# pov.net
KiCad netlist of a schematic drawn in EAGLE
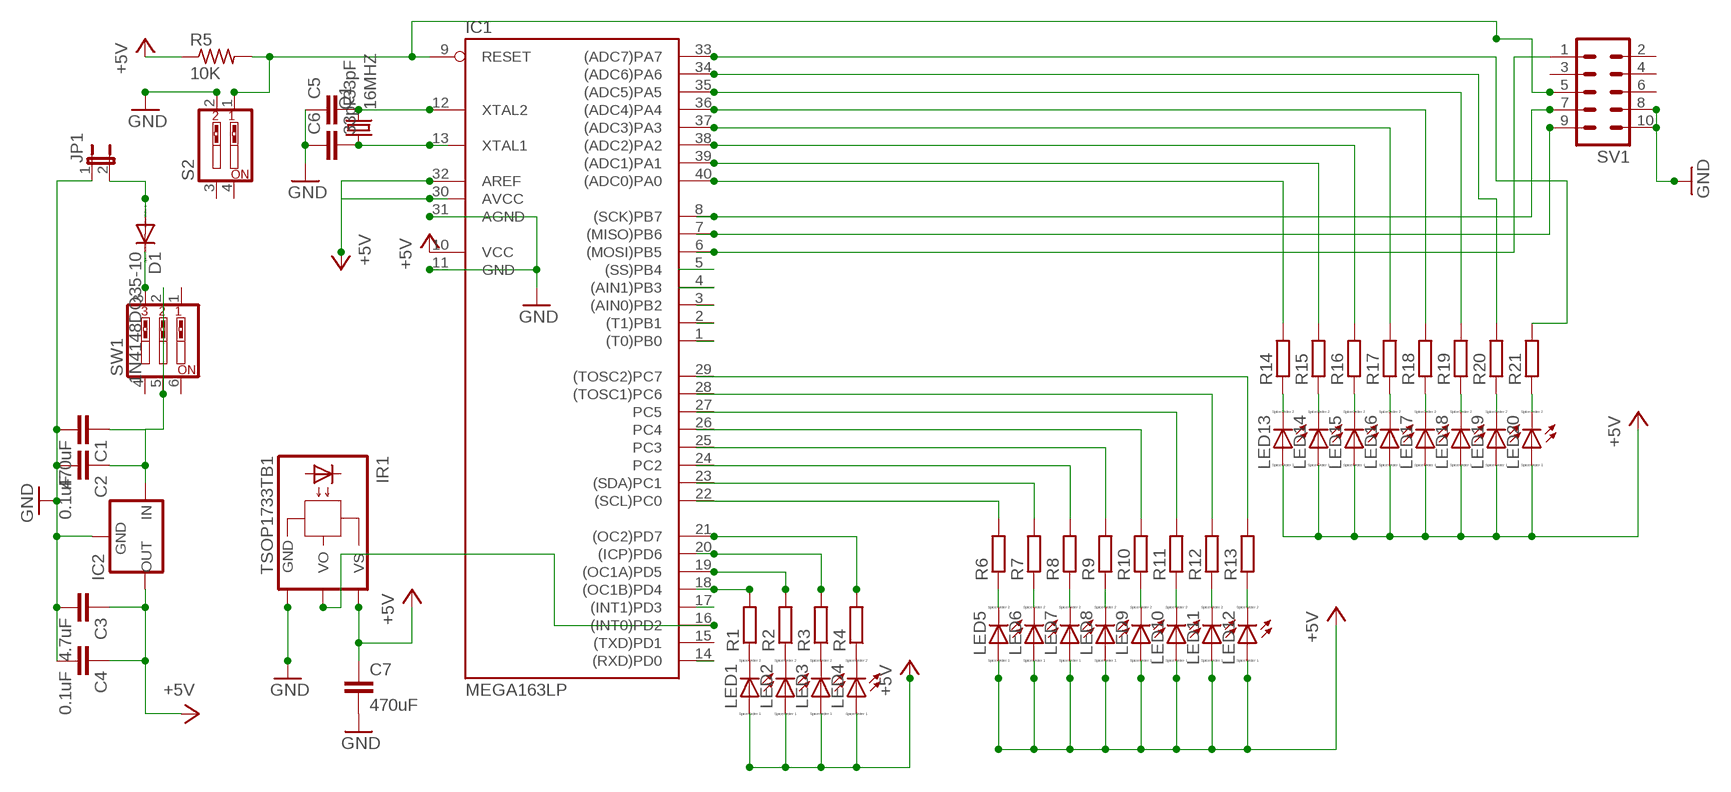
[diagram p0: schematic, sheet 1]

(export (version "E")
  (design (tool "Eeschema 10.0.6"))
  (components
    (comp (ref "C1")
      (value "470uF")
      (footprint "eagle-import:C2.5-4")
      (libsource (lib "eagle-import") (part "C2.5/4"))
    )
    (comp (ref "C2")
      (value "0.1uF")
      (footprint "eagle-import:C2.5-4")
      (libsource (lib "eagle-import") (part "C2.5/4"))
    )
    (comp (ref "C3")
      (value "4.7uF")
      (footprint "eagle-import:C2.5-4")
      (libsource (lib "eagle-import") (part "C2.5/4"))
    )
    (comp (ref "C4")
      (value "0.1uF")
      (footprint "eagle-import:C2.5-4")
      (libsource (lib "eagle-import") (part "C2.5/4"))
    )
    (comp (ref "C5")
      (value "33pF")
      (footprint "eagle-import:C2.5-4")
      (libsource (lib "eagle-import") (part "C2.5/4"))
    )
    (comp (ref "C6")
      (value "33pF")
      (footprint "eagle-import:C2.5-4")
      (libsource (lib "eagle-import") (part "C2.5/4"))
    )
    (comp (ref "C7")
      (value "470uF")
      (footprint "eagle-import:C2.5-4")
      (libsource (lib "eagle-import") (part "C2.5/4"))
    )
    (comp (ref "D1")
      (value "1N4148DO35-10")
      (footprint "eagle-import:DO35-10")
      (libsource (lib "eagle-import") (part "1N4148DO35-10"))
    )
    (comp (ref "IC1")
      (value "MEGA163LP")
      (footprint "eagle-import:DIL40")
      (libsource (lib "eagle-import") (part "MEGA163PL"))
    )
    (comp (ref "IC2")
      (value "78XXS")
      (footprint "eagle-import:78XXS")
      (libsource (lib "eagle-import") (part "78XXS"))
    )
    (comp (ref "IR1")
      (value "TSOP1733TB1")
      (footprint "eagle-import:TSOP17_TB1")
      (libsource (lib "eagle-import") (part "TSOP17TB133"))
    )
    (comp (ref "JP1")
      (value "JP1E")
      (footprint "eagle-import:JP1")
      (libsource (lib "eagle-import") (part "JP1E"))
    )
    (comp (ref "LED1")
      (value "LED_ELD260")
      (footprint "eagle-import:LED_LD260")
      (libsource (lib "eagle-import") (part "LED_ELD260"))
    )
    (comp (ref "LED2")
      (value "LED_ELD260")
      (footprint "eagle-import:LED_LD260")
      (libsource (lib "eagle-import") (part "LED_ELD260"))
    )
    (comp (ref "LED3")
      (value "LED_ELD260")
      (footprint "eagle-import:LED_LD260")
      (libsource (lib "eagle-import") (part "LED_ELD260"))
    )
    (comp (ref "LED4")
      (value "LED_ELD260")
      (footprint "eagle-import:LED_LD260")
      (libsource (lib "eagle-import") (part "LED_ELD260"))
    )
    (comp (ref "LED5")
      (value "LED_ELD260")
      (footprint "eagle-import:LED_LD260")
      (libsource (lib "eagle-import") (part "LED_ELD260"))
    )
    (comp (ref "LED6")
      (value "LED_ELD260")
      (footprint "eagle-import:LED_LD260")
      (libsource (lib "eagle-import") (part "LED_ELD260"))
    )
    (comp (ref "LED7")
      (value "LED_ELD260")
      (footprint "eagle-import:LED_LD260")
      (libsource (lib "eagle-import") (part "LED_ELD260"))
    )
    (comp (ref "LED8")
      (value "LED_ELD260")
      (footprint "eagle-import:LED_LD260")
      (libsource (lib "eagle-import") (part "LED_ELD260"))
    )
    (comp (ref "LED9")
      (value "LED_ELD260")
      (footprint "eagle-import:LED_LD260")
      (libsource (lib "eagle-import") (part "LED_ELD260"))
    )
    (comp (ref "LED10")
      (value "LED_ELD260")
      (footprint "eagle-import:LED_LD260")
      (libsource (lib "eagle-import") (part "LED_ELD260"))
    )
    (comp (ref "LED11")
      (value "LED_ELD260")
      (footprint "eagle-import:LED_LD260")
      (libsource (lib "eagle-import") (part "LED_ELD260"))
    )
    (comp (ref "LED12")
      (value "LED_ELD260")
      (footprint "eagle-import:LED_LD260")
      (libsource (lib "eagle-import") (part "LED_ELD260"))
    )
    (comp (ref "LED13")
      (value "LED_ELD260")
      (footprint "eagle-import:LED_LD260")
      (libsource (lib "eagle-import") (part "LED_ELD260"))
    )
    (comp (ref "LED14")
      (value "LED_ELD260")
      (footprint "eagle-import:LED_LD260")
      (libsource (lib "eagle-import") (part "LED_ELD260"))
    )
    (comp (ref "LED15")
      (value "LED_ELD260")
      (footprint "eagle-import:LED_LD260")
      (libsource (lib "eagle-import") (part "LED_ELD260"))
    )
    (comp (ref "LED16")
      (value "LED_ELD260")
      (footprint "eagle-import:LED_LD260")
      (libsource (lib "eagle-import") (part "LED_ELD260"))
    )
    (comp (ref "LED17")
      (value "LED_ELD260")
      (footprint "eagle-import:LED_LD260")
      (libsource (lib "eagle-import") (part "LED_ELD260"))
    )
    (comp (ref "LED18")
      (value "LED_ELD260")
      (footprint "eagle-import:LED_LD260")
      (libsource (lib "eagle-import") (part "LED_ELD260"))
    )
    (comp (ref "LED19")
      (value "LED_ELD260")
      (footprint "eagle-import:LED_LD260")
      (libsource (lib "eagle-import") (part "LED_ELD260"))
    )
    (comp (ref "LED20")
      (value "LED_ELD260")
      (footprint "eagle-import:LED_LD260")
      (libsource (lib "eagle-import") (part "LED_ELD260"))
    )
    (comp (ref "Q1")
      (value "16MHZ")
      (footprint "eagle-import:HC49U-V")
      (libsource (lib "eagle-import") (part "CRYSTALHC49U-V"))
    )
    (comp (ref "R1")
      (value "R-EU_0207/7")
      (footprint "eagle-import:0207_7")
      (libsource (lib "eagle-import") (part "R-EU_0207/7"))
    )
    (comp (ref "R2")
      (value "R-EU_0207/7")
      (footprint "eagle-import:0207_7")
      (libsource (lib "eagle-import") (part "R-EU_0207/7"))
    )
    (comp (ref "R3")
      (value "R-EU_0207/7")
      (footprint "eagle-import:0207_7")
      (libsource (lib "eagle-import") (part "R-EU_0207/7"))
    )
    (comp (ref "R4")
      (value "R-EU_0207/7")
      (footprint "eagle-import:0207_7")
      (libsource (lib "eagle-import") (part "R-EU_0207/7"))
    )
    (comp (ref "R5")
      (value "10K")
      (footprint "eagle-import:0204_7")
      (libsource (lib "eagle-import") (part "R-US_0204/7"))
    )
    (comp (ref "R6")
      (value "R-EU_0207/7")
      (footprint "eagle-import:0207_7")
      (libsource (lib "eagle-import") (part "R-EU_0207/7"))
    )
    (comp (ref "R7")
      (value "R-EU_0207/7")
      (footprint "eagle-import:0207_7")
      (libsource (lib "eagle-import") (part "R-EU_0207/7"))
    )
    (comp (ref "R8")
      (value "R-EU_0207/7")
      (footprint "eagle-import:0207_7")
      (libsource (lib "eagle-import") (part "R-EU_0207/7"))
    )
    (comp (ref "R9")
      (value "R-EU_0207/7")
      (footprint "eagle-import:0207_7")
      (libsource (lib "eagle-import") (part "R-EU_0207/7"))
    )
    (comp (ref "R10")
      (value "R-EU_0207/7")
      (footprint "eagle-import:0207_7")
      (libsource (lib "eagle-import") (part "R-EU_0207/7"))
    )
    (comp (ref "R11")
      (value "R-EU_0207/7")
      (footprint "eagle-import:0207_7")
      (libsource (lib "eagle-import") (part "R-EU_0207/7"))
    )
    (comp (ref "R12")
      (value "R-EU_0207/7")
      (footprint "eagle-import:0207_7")
      (libsource (lib "eagle-import") (part "R-EU_0207/7"))
    )
    (comp (ref "R13")
      (value "R-EU_0207/7")
      (footprint "eagle-import:0207_7")
      (libsource (lib "eagle-import") (part "R-EU_0207/7"))
    )
    (comp (ref "R14")
      (value "R-EU_0207/7")
      (footprint "eagle-import:0207_7")
      (libsource (lib "eagle-import") (part "R-EU_0207/7"))
    )
    (comp (ref "R15")
      (value "R-EU_0207/7")
      (footprint "eagle-import:0207_7")
      (libsource (lib "eagle-import") (part "R-EU_0207/7"))
    )
    (comp (ref "R16")
      (value "R-EU_0207/7")
      (footprint "eagle-import:0207_7")
      (libsource (lib "eagle-import") (part "R-EU_0207/7"))
    )
    (comp (ref "R17")
      (value "R-EU_0207/7")
      (footprint "eagle-import:0207_7")
      (libsource (lib "eagle-import") (part "R-EU_0207/7"))
    )
    (comp (ref "R18")
      (value "R-EU_0207/7")
      (footprint "eagle-import:0207_7")
      (libsource (lib "eagle-import") (part "R-EU_0207/7"))
    )
    (comp (ref "R19")
      (value "R-EU_0207/7")
      (footprint "eagle-import:0207_7")
      (libsource (lib "eagle-import") (part "R-EU_0207/7"))
    )
    (comp (ref "R20")
      (value "R-EU_0207/7")
      (footprint "eagle-import:0207_7")
      (libsource (lib "eagle-import") (part "R-EU_0207/7"))
    )
    (comp (ref "R21")
      (value "R-EU_0207/7")
      (footprint "eagle-import:0207_7")
      (libsource (lib "eagle-import") (part "R-EU_0207/7"))
    )
    (comp (ref "S2")
      (value "SW_DIP-2")
      (footprint "eagle-import:EDG-02")
      (libsource (lib "eagle-import") (part "SW_DIP-2"))
    )
    (comp (ref "SV1")
      (value "MA05-2")
      (footprint "eagle-import:MA05-2")
      (libsource (lib "eagle-import") (part "MA05-2"))
    )
    (comp (ref "SW1")
      (value "SW_DIP-3")
      (footprint "eagle-import:EDG-03")
      (libsource (lib "eagle-import") (part "SW_DIP-3"))
    )
  )
  (nets
    (net (code "1") (name "+5V") (class "Default")
      (node (ref "C3") (pin "1") (pinfunction "1_1") (pintype "passive"))
      (node (ref "C4") (pin "1") (pinfunction "1_1") (pintype "passive"))
      (node (ref "C7") (pin "1") (pinfunction "1_1") (pintype "passive"))
      (node (ref "IC1") (pin "10") (pinfunction "VCC_10") (pintype "power_in"))
      (node (ref "IC1") (pin "30") (pinfunction "AVCC_30") (pintype "power_in"))
      (node (ref "IC1") (pin "32") (pinfunction "AREF_32") (pintype "passive"))
      (node (ref "IC2") (pin "OUT") (pinfunction "OUT_OUT") (pintype "passive"))
      (node (ref "IR1") (pin "VS") (pinfunction "VS_VS") (pintype "power_in"))
      (node (ref "LED1") (pin "A") (pinfunction "A_A") (pintype "passive"))
      (node (ref "LED10") (pin "A") (pinfunction "A_A") (pintype "passive"))
      (node (ref "LED11") (pin "A") (pinfunction "A_A") (pintype "passive"))
      (node (ref "LED12") (pin "A") (pinfunction "A_A") (pintype "passive"))
      (node (ref "LED13") (pin "A") (pinfunction "A_A") (pintype "passive"))
      (node (ref "LED14") (pin "A") (pinfunction "A_A") (pintype "passive"))
      (node (ref "LED15") (pin "A") (pinfunction "A_A") (pintype "passive"))
      (node (ref "LED16") (pin "A") (pinfunction "A_A") (pintype "passive"))
      (node (ref "LED17") (pin "A") (pinfunction "A_A") (pintype "passive"))
      (node (ref "LED18") (pin "A") (pinfunction "A_A") (pintype "passive"))
      (node (ref "LED19") (pin "A") (pinfunction "A_A") (pintype "passive"))
      (node (ref "LED2") (pin "A") (pinfunction "A_A") (pintype "passive"))
      (node (ref "LED20") (pin "A") (pinfunction "A_A") (pintype "passive"))
      (node (ref "LED3") (pin "A") (pinfunction "A_A") (pintype "passive"))
      (node (ref "LED4") (pin "A") (pinfunction "A_A") (pintype "passive"))
      (node (ref "LED5") (pin "A") (pinfunction "A_A") (pintype "passive"))
      (node (ref "LED6") (pin "A") (pinfunction "A_A") (pintype "passive"))
      (node (ref "LED7") (pin "A") (pinfunction "A_A") (pintype "passive"))
      (node (ref "LED8") (pin "A") (pinfunction "A_A") (pintype "passive"))
      (node (ref "LED9") (pin "A") (pinfunction "A_A") (pintype "passive"))
      (node (ref "R5") (pin "1") (pinfunction "1_1") (pintype "passive"))
    )
    (net (code "2") (name "GND") (class "Default")
      (node (ref "C1") (pin "2") (pinfunction "2_2") (pintype "passive"))
      (node (ref "C2") (pin "2") (pinfunction "2_2") (pintype "passive"))
      (node (ref "C3") (pin "2") (pinfunction "2_2") (pintype "passive"))
      (node (ref "C4") (pin "2") (pinfunction "2_2") (pintype "passive"))
      (node (ref "C5") (pin "1") (pinfunction "1_1") (pintype "passive"))
      (node (ref "C6") (pin "1") (pinfunction "1_1") (pintype "passive"))
      (node (ref "C7") (pin "2") (pinfunction "2_2") (pintype "passive"))
      (node (ref "IC1") (pin "11") (pinfunction "GND_11") (pintype "power_in"))
      (node (ref "IC1") (pin "31") (pinfunction "AGND_31") (pintype "power_in"))
      (node (ref "IC2") (pin "GND") (pinfunction "GND_GND") (pintype "input"))
      (node (ref "IR1") (pin "GND") (pinfunction "GND_GND") (pintype "power_in"))
      (node (ref "JP1") (pin "1") (pinfunction "1_1") (pintype "passive"))
      (node (ref "S2") (pin "2") (pinfunction "2_2") (pintype "passive"))
      (node (ref "SV1") (pin "10") (pinfunction "10_10") (pintype "passive"))
      (node (ref "SV1") (pin "8") (pinfunction "8_8") (pintype "passive"))
    )
    (net (code "3") (name "Net-(C1-Pad1)") (class "Default")
      (node (ref "C1") (pin "1") (pinfunction "1_1") (pintype "passive"))
      (node (ref "C2") (pin "1") (pinfunction "1_1") (pintype "passive"))
      (node (ref "IC2") (pin "IN") (pinfunction "IN_IN") (pintype "input"))
      (node (ref "SW1") (pin "2") (pinfunction "2_2") (pintype "passive"))
      (node (ref "SW1") (pin "5") (pinfunction "5_5") (pintype "passive"))
    )
    (net (code "4") (name "Net-(D1-PadA)") (class "Default")
      (node (ref "D1") (pin "A") (pinfunction "A_A") (pintype "passive"))
      (node (ref "JP1") (pin "2") (pinfunction "2_2") (pintype "passive"))
    )
    (net (code "5") (name "Net-(D1-PadC)") (class "Default")
      (node (ref "D1") (pin "C") (pinfunction "C_C") (pintype "passive"))
      (node (ref "SW1") (pin "3") (pinfunction "3_3") (pintype "passive"))
    )
    (net (code "6") (name "Net-(IC1-(ADC0)PA0)") (class "Default")
      (node (ref "IC1") (pin "40") (pinfunction "(ADC0)PA0_40") (pintype "bidirectional"))
      (node (ref "R14") (pin "2") (pinfunction "2_2") (pintype "passive"))
    )
    (net (code "7") (name "Net-(IC1-(ADC1)PA1)") (class "Default")
      (node (ref "IC1") (pin "39") (pinfunction "(ADC1)PA1_39") (pintype "bidirectional"))
      (node (ref "R15") (pin "2") (pinfunction "2_2") (pintype "passive"))
    )
    (net (code "8") (name "Net-(IC1-(ADC2)PA2)") (class "Default")
      (node (ref "IC1") (pin "38") (pinfunction "(ADC2)PA2_38") (pintype "bidirectional"))
      (node (ref "R16") (pin "2") (pinfunction "2_2") (pintype "passive"))
    )
    (net (code "9") (name "Net-(IC1-(ADC3)PA3)") (class "Default")
      (node (ref "IC1") (pin "37") (pinfunction "(ADC3)PA3_37") (pintype "bidirectional"))
      (node (ref "R17") (pin "2") (pinfunction "2_2") (pintype "passive"))
    )
    (net (code "10") (name "Net-(IC1-(ADC4)PA4)") (class "Default")
      (node (ref "IC1") (pin "36") (pinfunction "(ADC4)PA4_36") (pintype "bidirectional"))
      (node (ref "R18") (pin "2") (pinfunction "2_2") (pintype "passive"))
    )
    (net (code "11") (name "Net-(IC1-(ADC5)PA5)") (class "Default")
      (node (ref "IC1") (pin "35") (pinfunction "(ADC5)PA5_35") (pintype "bidirectional"))
      (node (ref "R19") (pin "2") (pinfunction "2_2") (pintype "passive"))
    )
    (net (code "12") (name "Net-(IC1-(ADC6)PA6)") (class "Default")
      (node (ref "IC1") (pin "34") (pinfunction "(ADC6)PA6_34") (pintype "bidirectional"))
      (node (ref "R20") (pin "2") (pinfunction "2_2") (pintype "passive"))
    )
    (net (code "13") (name "Net-(IC1-(ADC7)PA7)") (class "Default")
      (node (ref "IC1") (pin "33") (pinfunction "(ADC7)PA7_33") (pintype "bidirectional"))
      (node (ref "R21") (pin "2") (pinfunction "2_2") (pintype "passive"))
    )
    (net (code "14") (name "Net-(IC1-(ICP)PD6)") (class "Default")
      (node (ref "IC1") (pin "20") (pinfunction "(ICP)PD6_20") (pintype "bidirectional"))
      (node (ref "R3") (pin "2") (pinfunction "2_2") (pintype "passive"))
    )
    (net (code "15") (name "Net-(IC1-(INT0)PD2)") (class "Default")
      (node (ref "IC1") (pin "16") (pinfunction "(INT0)PD2_16") (pintype "bidirectional"))
      (node (ref "IR1") (pin "VO") (pinfunction "VO_VO") (pintype "open_collector"))
    )
    (net (code "16") (name "Net-(IC1-(MISO)PB6)") (class "Default")
      (node (ref "IC1") (pin "7") (pinfunction "(MISO)PB6_7") (pintype "bidirectional"))
      (node (ref "SV1") (pin "9") (pinfunction "9_9") (pintype "passive"))
    )
    (net (code "17") (name "Net-(IC1-(MOSI)PB5)") (class "Default")
      (node (ref "IC1") (pin "6") (pinfunction "(MOSI)PB5_6") (pintype "bidirectional"))
      (node (ref "SV1") (pin "1") (pinfunction "1_1") (pintype "passive"))
    )
    (net (code "18") (name "Net-(IC1-(OC1A)PD5)") (class "Default")
      (node (ref "IC1") (pin "19") (pinfunction "(OC1A)PD5_19") (pintype "bidirectional"))
      (node (ref "R2") (pin "2") (pinfunction "2_2") (pintype "passive"))
    )
    (net (code "19") (name "Net-(IC1-(OC1B)PD4)") (class "Default")
      (node (ref "IC1") (pin "18") (pinfunction "(OC1B)PD4_18") (pintype "bidirectional"))
      (node (ref "R1") (pin "2") (pinfunction "2_2") (pintype "passive"))
    )
    (net (code "20") (name "Net-(IC1-(OC2)PD7)") (class "Default")
      (node (ref "IC1") (pin "21") (pinfunction "(OC2)PD7_21") (pintype "bidirectional"))
      (node (ref "R4") (pin "2") (pinfunction "2_2") (pintype "passive"))
    )
    (net (code "21") (name "Net-(IC1-(SCK)PB7)") (class "Default")
      (node (ref "IC1") (pin "8") (pinfunction "(SCK)PB7_8") (pintype "bidirectional"))
      (node (ref "SV1") (pin "7") (pinfunction "7_7") (pintype "passive"))
    )
    (net (code "22") (name "Net-(IC1-(SCL)PC0)") (class "Default")
      (node (ref "IC1") (pin "22") (pinfunction "(SCL)PC0_22") (pintype "bidirectional"))
      (node (ref "R6") (pin "2") (pinfunction "2_2") (pintype "passive"))
    )
    (net (code "23") (name "Net-(IC1-(SDA)PC1)") (class "Default")
      (node (ref "IC1") (pin "23") (pinfunction "(SDA)PC1_23") (pintype "bidirectional"))
      (node (ref "R7") (pin "2") (pinfunction "2_2") (pintype "passive"))
    )
    (net (code "24") (name "Net-(IC1-(TOSC1)PC6)") (class "Default")
      (node (ref "IC1") (pin "28") (pinfunction "(TOSC1)PC6_28") (pintype "bidirectional"))
      (node (ref "R12") (pin "2") (pinfunction "2_2") (pintype "passive"))
    )
    (net (code "25") (name "Net-(IC1-(TOSC2)PC7)") (class "Default")
      (node (ref "IC1") (pin "29") (pinfunction "(TOSC2)PC7_29") (pintype "bidirectional"))
      (node (ref "R13") (pin "2") (pinfunction "2_2") (pintype "passive"))
    )
    (net (code "26") (name "Net-(IC1-PC2)") (class "Default")
      (node (ref "IC1") (pin "24") (pinfunction "PC2_24") (pintype "bidirectional"))
      (node (ref "R8") (pin "2") (pinfunction "2_2") (pintype "passive"))
    )
    (net (code "27") (name "Net-(IC1-PC3)") (class "Default")
      (node (ref "IC1") (pin "25") (pinfunction "PC3_25") (pintype "bidirectional"))
      (node (ref "R9") (pin "2") (pinfunction "2_2") (pintype "passive"))
    )
    (net (code "28") (name "Net-(IC1-PC4)") (class "Default")
      (node (ref "IC1") (pin "26") (pinfunction "PC4_26") (pintype "bidirectional"))
      (node (ref "R10") (pin "2") (pinfunction "2_2") (pintype "passive"))
    )
    (net (code "29") (name "Net-(IC1-PC5)") (class "Default")
      (node (ref "IC1") (pin "27") (pinfunction "PC5_27") (pintype "bidirectional"))
      (node (ref "R11") (pin "2") (pinfunction "2_2") (pintype "passive"))
    )
    (net (code "30") (name "Net-(IC1-RESET)") (class "Default")
      (node (ref "IC1") (pin "9") (pinfunction "RESET_9") (pintype "input"))
      (node (ref "R5") (pin "2") (pinfunction "2_2") (pintype "passive"))
      (node (ref "S2") (pin "1") (pinfunction "1_1") (pintype "passive"))
      (node (ref "SV1") (pin "5") (pinfunction "5_5") (pintype "passive"))
    )
    (net (code "31") (name "Net-(IC1-XTAL1)") (class "Default")
      (node (ref "C6") (pin "2") (pinfunction "2_2") (pintype "passive"))
      (node (ref "IC1") (pin "13") (pinfunction "XTAL1_13") (pintype "bidirectional"))
      (node (ref "Q1") (pin "1") (pinfunction "1_1") (pintype "passive"))
    )
    (net (code "32") (name "Net-(IC1-XTAL2)") (class "Default")
      (node (ref "C5") (pin "2") (pinfunction "2_2") (pintype "passive"))
      (node (ref "IC1") (pin "12") (pinfunction "XTAL2_12") (pintype "bidirectional"))
      (node (ref "Q1") (pin "2") (pinfunction "2_2") (pintype "passive"))
    )
    (net (code "33") (name "Net-(LED1-C)") (class "Default")
      (node (ref "LED1") (pin "K") (pinfunction "C_K") (pintype "passive"))
      (node (ref "R1") (pin "1") (pinfunction "1_1") (pintype "passive"))
    )
    (net (code "34") (name "Net-(LED2-C)") (class "Default")
      (node (ref "LED2") (pin "K") (pinfunction "C_K") (pintype "passive"))
      (node (ref "R2") (pin "1") (pinfunction "1_1") (pintype "passive"))
    )
    (net (code "35") (name "Net-(LED3-C)") (class "Default")
      (node (ref "LED3") (pin "K") (pinfunction "C_K") (pintype "passive"))
      (node (ref "R3") (pin "1") (pinfunction "1_1") (pintype "passive"))
    )
    (net (code "36") (name "Net-(LED4-C)") (class "Default")
      (node (ref "LED4") (pin "K") (pinfunction "C_K") (pintype "passive"))
      (node (ref "R4") (pin "1") (pinfunction "1_1") (pintype "passive"))
    )
    (net (code "37") (name "Net-(LED5-C)") (class "Default")
      (node (ref "LED5") (pin "K") (pinfunction "C_K") (pintype "passive"))
      (node (ref "R6") (pin "1") (pinfunction "1_1") (pintype "passive"))
    )
    (net (code "38") (name "Net-(LED6-C)") (class "Default")
      (node (ref "LED6") (pin "K") (pinfunction "C_K") (pintype "passive"))
      (node (ref "R7") (pin "1") (pinfunction "1_1") (pintype "passive"))
    )
    (net (code "39") (name "Net-(LED7-C)") (class "Default")
      (node (ref "LED7") (pin "K") (pinfunction "C_K") (pintype "passive"))
      (node (ref "R8") (pin "1") (pinfunction "1_1") (pintype "passive"))
    )
    (net (code "40") (name "Net-(LED8-C)") (class "Default")
      (node (ref "LED8") (pin "K") (pinfunction "C_K") (pintype "passive"))
      (node (ref "R9") (pin "1") (pinfunction "1_1") (pintype "passive"))
    )
    (net (code "41") (name "Net-(LED9-C)") (class "Default")
      (node (ref "LED9") (pin "K") (pinfunction "C_K") (pintype "passive"))
      (node (ref "R10") (pin "1") (pinfunction "1_1") (pintype "passive"))
    )
    (net (code "42") (name "Net-(LED10-C)") (class "Default")
      (node (ref "LED10") (pin "K") (pinfunction "C_K") (pintype "passive"))
      (node (ref "R11") (pin "1") (pinfunction "1_1") (pintype "passive"))
    )
    (net (code "43") (name "Net-(LED11-C)") (class "Default")
      (node (ref "LED11") (pin "K") (pinfunction "C_K") (pintype "passive"))
      (node (ref "R12") (pin "1") (pinfunction "1_1") (pintype "passive"))
    )
    (net (code "44") (name "Net-(LED12-C)") (class "Default")
      (node (ref "LED12") (pin "K") (pinfunction "C_K") (pintype "passive"))
      (node (ref "R13") (pin "1") (pinfunction "1_1") (pintype "passive"))
    )
    (net (code "45") (name "Net-(LED13-C)") (class "Default")
      (node (ref "LED13") (pin "K") (pinfunction "C_K") (pintype "passive"))
      (node (ref "R14") (pin "1") (pinfunction "1_1") (pintype "passive"))
    )
    (net (code "46") (name "Net-(LED14-C)") (class "Default")
      (node (ref "LED14") (pin "K") (pinfunction "C_K") (pintype "passive"))
      (node (ref "R15") (pin "1") (pinfunction "1_1") (pintype "passive"))
    )
    (net (code "47") (name "Net-(LED15-C)") (class "Default")
      (node (ref "LED15") (pin "K") (pinfunction "C_K") (pintype "passive"))
      (node (ref "R16") (pin "1") (pinfunction "1_1") (pintype "passive"))
    )
    (net (code "48") (name "Net-(LED16-C)") (class "Default")
      (node (ref "LED16") (pin "K") (pinfunction "C_K") (pintype "passive"))
      (node (ref "R17") (pin "1") (pinfunction "1_1") (pintype "passive"))
    )
    (net (code "49") (name "Net-(LED17-C)") (class "Default")
      (node (ref "LED17") (pin "K") (pinfunction "C_K") (pintype "passive"))
      (node (ref "R18") (pin "1") (pinfunction "1_1") (pintype "passive"))
    )
    (net (code "50") (name "Net-(LED18-C)") (class "Default")
      (node (ref "LED18") (pin "K") (pinfunction "C_K") (pintype "passive"))
      (node (ref "R19") (pin "1") (pinfunction "1_1") (pintype "passive"))
    )
    (net (code "51") (name "Net-(LED19-C)") (class "Default")
      (node (ref "LED19") (pin "K") (pinfunction "C_K") (pintype "passive"))
      (node (ref "R20") (pin "1") (pinfunction "1_1") (pintype "passive"))
    )
    (net (code "52") (name "Net-(LED20-C)") (class "Default")
      (node (ref "LED20") (pin "K") (pinfunction "C_K") (pintype "passive"))
      (node (ref "R21") (pin "1") (pinfunction "1_1") (pintype "passive"))
    )
    (net (code "53") (name "unconnected-(IC1-(AIN0)PB2-Pad3)") (class "Default")
      (node (ref "IC1") (pin "3") (pinfunction "(AIN0)PB2_3") (pintype "bidirectional"))
    )
    (net (code "54") (name "unconnected-(IC1-(AIN1)PB3-Pad4)") (class "Default")
      (node (ref "IC1") (pin "4") (pinfunction "(AIN1)PB3_4") (pintype "bidirectional"))
    )
    (net (code "55") (name "unconnected-(IC1-(INT1)PD3-Pad17)") (class "Default")
      (node (ref "IC1") (pin "17") (pinfunction "(INT1)PD3_17") (pintype "bidirectional"))
    )
    (net (code "56") (name "unconnected-(IC1-(RXD)PD0-Pad14)") (class "Default")
      (node (ref "IC1") (pin "14") (pinfunction "(RXD)PD0_14") (pintype "bidirectional"))
    )
    (net (code "57") (name "unconnected-(IC1-(SS)PB4-Pad5)") (class "Default")
      (node (ref "IC1") (pin "5") (pinfunction "(SS)PB4_5") (pintype "bidirectional"))
    )
    (net (code "58") (name "unconnected-(IC1-(T0)PB0-Pad1)") (class "Default")
      (node (ref "IC1") (pin "1") (pinfunction "(T0)PB0_1") (pintype "bidirectional"))
    )
    (net (code "59") (name "unconnected-(IC1-(T1)PB1-Pad2)") (class "Default")
      (node (ref "IC1") (pin "2") (pinfunction "(T1)PB1_2") (pintype "bidirectional"))
    )
    (net (code "60") (name "unconnected-(IC1-(TXD)PD1-Pad15)") (class "Default")
      (node (ref "IC1") (pin "15") (pinfunction "(TXD)PD1_15") (pintype "bidirectional"))
    )
    (net (code "61") (name "unconnected-(S2-Pad3)") (class "Default")
      (node (ref "S2") (pin "3") (pinfunction "3_3") (pintype "passive"))
    )
    (net (code "62") (name "unconnected-(S2-Pad4)") (class "Default")
      (node (ref "S2") (pin "4") (pinfunction "4_4") (pintype "passive"))
    )
    (net (code "63") (name "unconnected-(SV1-Pad2)") (class "Default")
      (node (ref "SV1") (pin "2") (pinfunction "2_2") (pintype "passive"))
    )
    (net (code "64") (name "unconnected-(SV1-Pad3)") (class "Default")
      (node (ref "SV1") (pin "3") (pinfunction "3_3") (pintype "passive"))
    )
    (net (code "65") (name "unconnected-(SV1-Pad4)") (class "Default")
      (node (ref "SV1") (pin "4") (pinfunction "4_4") (pintype "passive"))
    )
    (net (code "66") (name "unconnected-(SV1-Pad6)") (class "Default")
      (node (ref "SV1") (pin "6") (pinfunction "6_6") (pintype "passive"))
    )
    (net (code "67") (name "unconnected-(SW1-Pad1)") (class "Default")
      (node (ref "SW1") (pin "1") (pinfunction "1_1") (pintype "passive"))
    )
    (net (code "68") (name "unconnected-(SW1-Pad4)") (class "Default")
      (node (ref "SW1") (pin "4") (pinfunction "4_4") (pintype "passive"))
    )
    (net (code "69") (name "unconnected-(SW1-Pad6)") (class "Default")
      (node (ref "SW1") (pin "6") (pinfunction "6_6") (pintype "passive"))
    )
  )
)
